# PCB-OLEDROCKER.net
KiCad netlist of a schematic drawn in EAGLE
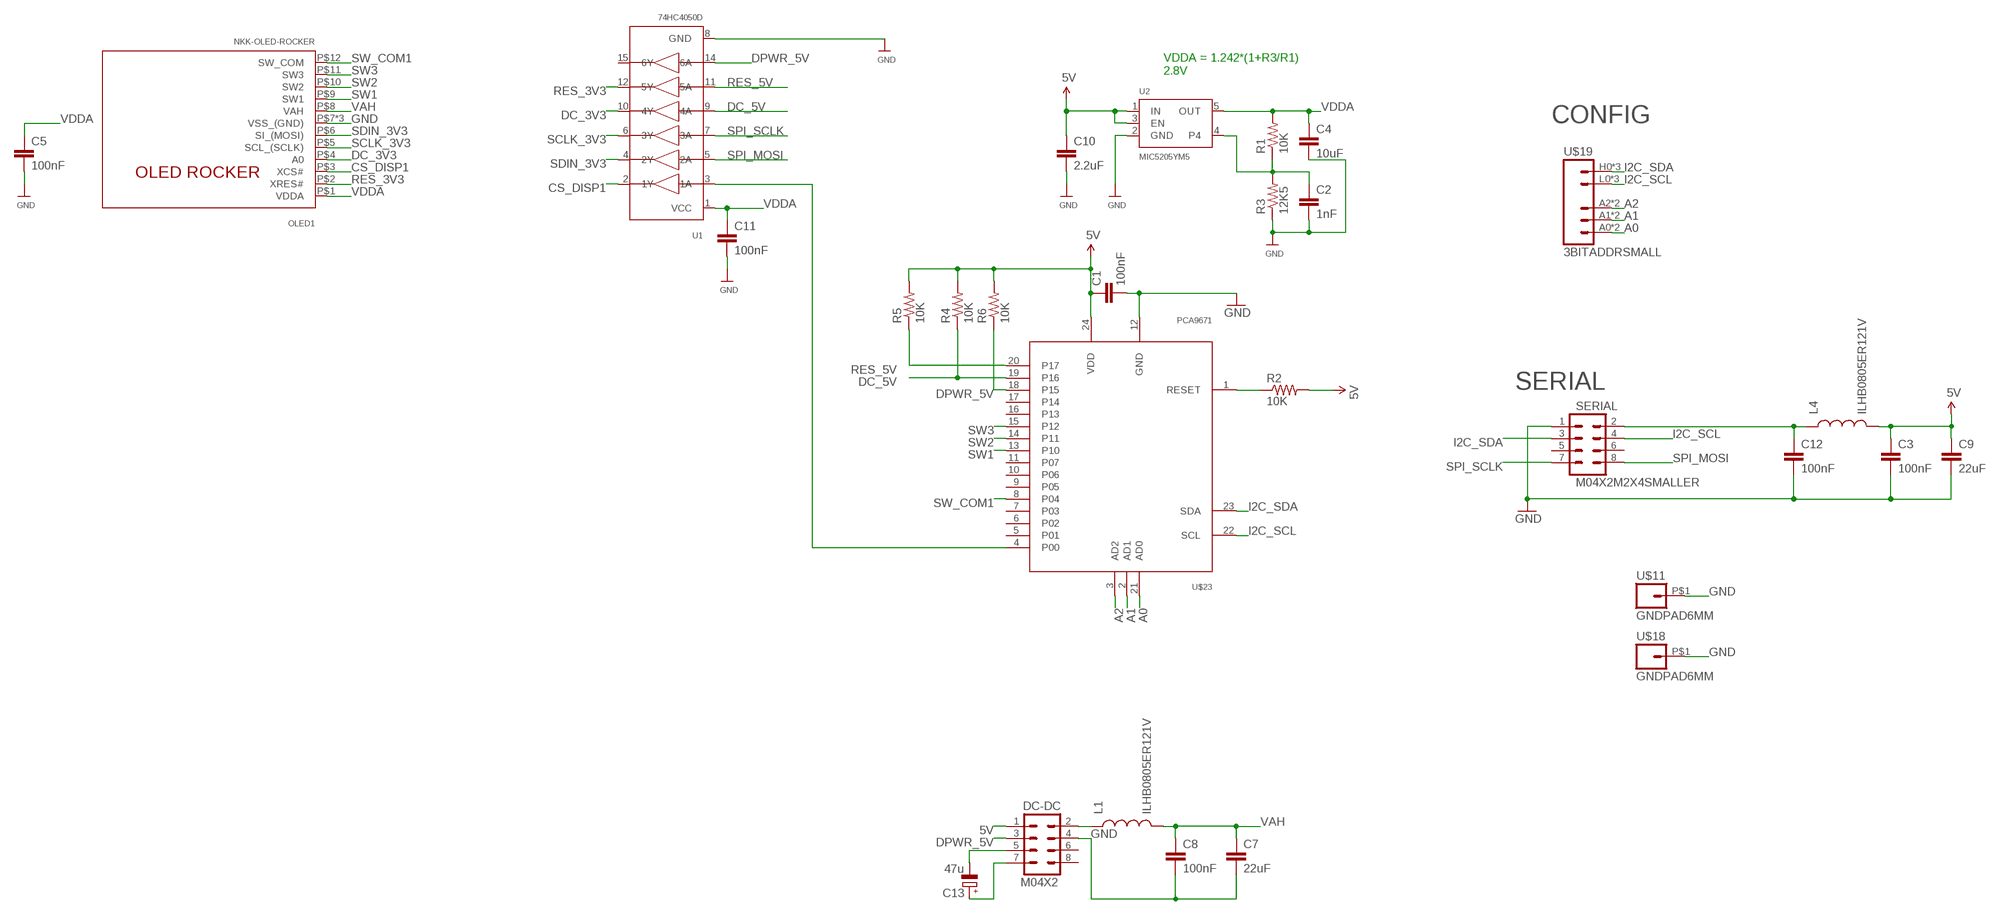
[diagram p0: schematic, sheet 1]

(export (version "E")
  (design (tool "Eeschema 10.0.6"))
  (components
    (comp (ref "C1")
      (value "100nF")
      (footprint "eagle-import:0603-CAP")
      (libsource (lib "eagle-import") (part "CAP0603-CAP"))
    )
    (comp (ref "C2")
      (value "1nF")
      (footprint "eagle-import:0603-CAP")
      (libsource (lib "eagle-import") (part "CAP0603-CAP"))
    )
    (comp (ref "C3")
      (value "100nF")
      (footprint "eagle-import:0603-CAP")
      (libsource (lib "eagle-import") (part "CAP0603-CAP"))
    )
    (comp (ref "C4")
      (value "10uF")
      (footprint "eagle-import:0805")
      (libsource (lib "eagle-import") (part "CAP0805"))
    )
    (comp (ref "C5")
      (value "100nF")
      (footprint "eagle-import:0603-CAP")
      (libsource (lib "eagle-import") (part "CAP0603-CAP"))
    )
    (comp (ref "C7")
      (value "22uF")
      (footprint "eagle-import:0805")
      (libsource (lib "eagle-import") (part "CAP0805"))
    )
    (comp (ref "C8")
      (value "100nF")
      (footprint "eagle-import:0603-CAP")
      (libsource (lib "eagle-import") (part "CAP0603-CAP"))
    )
    (comp (ref "C9")
      (value "22uF")
      (footprint "eagle-import:0805")
      (libsource (lib "eagle-import") (part "CAP0805"))
    )
    (comp (ref "C10")
      (value "2.2uF")
      (footprint "eagle-import:0603-CAP")
      (libsource (lib "eagle-import") (part "CAP0603-CAP"))
    )
    (comp (ref "C11")
      (value "100nF")
      (footprint "eagle-import:0603-CAP")
      (libsource (lib "eagle-import") (part "CAP0603-CAP"))
    )
    (comp (ref "C12")
      (value "100nF")
      (footprint "eagle-import:0603-CAP")
      (libsource (lib "eagle-import") (part "CAP0603-CAP"))
    )
    (comp (ref "C13")
      (value "47u")
      (footprint "eagle-import:PANASONIC_D")
      (libsource (lib "eagle-import") (part "CPOL-EUD"))
    )
    (comp (ref "DC-DC")
      (value "M04X2")
      (footprint "eagle-import:2X4")
      (libsource (lib "eagle-import") (part "SparkFun_M04X2"))
    )
    (comp (ref "L1")
      (value "ILHB0805ER121V")
      (footprint "eagle-import:0805")
      (libsource (lib "eagle-import") (part "INDUCTOR0805"))
    )
    (comp (ref "L4")
      (value "ILHB0805ER121V")
      (footprint "eagle-import:0805")
      (libsource (lib "eagle-import") (part "INDUCTOR0805"))
    )
    (comp (ref "OLED1")
      (value "NKK-OLED-ROCKER")
      (footprint "eagle-import:JST_BM12B-SURS")
      (libsource (lib "eagle-import") (part "NKK-OLED-ROCKER"))
    )
    (comp (ref "R1")
      (value "10K")
      (footprint "eagle-import:0603-RES")
      (libsource (lib "eagle-import") (part "RESISTOR0603-RES"))
    )
    (comp (ref "R2")
      (value "10K")
      (footprint "eagle-import:0603-RES")
      (libsource (lib "eagle-import") (part "RESISTOR0603-RES"))
    )
    (comp (ref "R3")
      (value "12K5")
      (footprint "eagle-import:0603-RES")
      (libsource (lib "eagle-import") (part "RESISTOR0603-RES"))
    )
    (comp (ref "R4")
      (value "10K")
      (footprint "eagle-import:0603-RES")
      (libsource (lib "eagle-import") (part "RESISTOR0603-RES"))
    )
    (comp (ref "R5")
      (value "10K")
      (footprint "eagle-import:0603-RES")
      (libsource (lib "eagle-import") (part "RESISTOR0603-RES"))
    )
    (comp (ref "R6")
      (value "10K")
      (footprint "eagle-import:0603-RES")
      (libsource (lib "eagle-import") (part "RESISTOR0603-RES"))
    )
    (comp (ref "SERIAL")
      (value "M04X2M2X4SMALLER")
      (footprint "eagle-import:M2X4SMALLER")
      (libsource (lib "eagle-import") (part "M04X2M2X4SMALLER"))
    )
    (comp (ref "U$11")
      (value "GNDPAD6MM")
      (footprint "eagle-import:3.2MMPAD6MM")
      (libsource (lib "eagle-import") (part "GNDPAD6MM"))
    )
    (comp (ref "U$18")
      (value "GNDPAD6MM")
      (footprint "eagle-import:3.2MMPAD6MM")
      (libsource (lib "eagle-import") (part "GNDPAD6MM"))
    )
    (comp (ref "U$19")
      (value "3BITADDRSMALL")
      (footprint "eagle-import:3BITADDR_SMALL")
      (libsource (lib "eagle-import") (part "3BITADDRSMALL"))
    )
    (comp (ref "U$23")
      (value "PCA9671")
      (footprint "eagle-import:TSSOP24")
      (libsource (lib "eagle-import") (part "PCA9671"))
    )
    (comp (ref "U1")
      (value "74HC4050D")
      (footprint "eagle-import:TSSOP16")
      (libsource (lib "eagle-import") (part "74HC4050DTSSOP16"))
    )
    (comp (ref "U2")
      (value "MIC5205YM5")
      (footprint "eagle-import:SOT23-5")
      (libsource (lib "eagle-import") (part "VREG_SOT23-5"))
    )
  )
  (nets
    (net (code "1") (name "5V") (class "Default")
      (node (ref "C1") (pin "1") (pinfunction "1_1") (pintype "passive"))
      (node (ref "C10") (pin "1") (pinfunction "1_1") (pintype "passive"))
      (node (ref "C3") (pin "1") (pinfunction "1_1") (pintype "passive"))
      (node (ref "C9") (pin "1") (pinfunction "1_1") (pintype "passive"))
      (node (ref "DC-DC") (pin "1") (pinfunction "1_1") (pintype "passive"))
      (node (ref "L4") (pin "2") (pinfunction "2_2") (pintype "passive"))
      (node (ref "R2") (pin "2") (pinfunction "2_2") (pintype "passive"))
      (node (ref "R4") (pin "2") (pinfunction "2_2") (pintype "passive"))
      (node (ref "R5") (pin "2") (pinfunction "2_2") (pintype "passive"))
      (node (ref "R6") (pin "2") (pinfunction "2_2") (pintype "passive"))
      (node (ref "U$23") (pin "24") (pinfunction "VDD_24") (pintype "power_in"))
      (node (ref "U2") (pin "1") (pinfunction "IN_1") (pintype "bidirectional"))
      (node (ref "U2") (pin "3") (pinfunction "EN_3") (pintype "bidirectional"))
    )
    (net (code "2") (name "A0") (class "Default")
      (node (ref "U$19") (pin "A0") (pinfunction "A0_A0") (pintype "passive"))
      (node (ref "U$19") (pin "AS0") (pinfunction "A0_AS0") (pintype "passive"))
      (node (ref "U$23") (pin "21") (pinfunction "AD0_21") (pintype "input"))
    )
    (net (code "3") (name "A1") (class "Default")
      (node (ref "U$19") (pin "A1") (pinfunction "A1_A1") (pintype "passive"))
      (node (ref "U$19") (pin "AS1") (pinfunction "A1_AS1") (pintype "passive"))
      (node (ref "U$23") (pin "2") (pinfunction "AD1_2") (pintype "input"))
    )
    (net (code "4") (name "A2") (class "Default")
      (node (ref "U$19") (pin "A2") (pinfunction "A2_A2") (pintype "passive"))
      (node (ref "U$19") (pin "AS2") (pinfunction "A2_AS2") (pintype "passive"))
      (node (ref "U$23") (pin "3") (pinfunction "AD2_3") (pintype "input"))
    )
    (net (code "5") (name "CS_DISP1") (class "Default")
      (node (ref "OLED1") (pin "P$3") (pinfunction "XCS#_P$3") (pintype "input"))
      (node (ref "U1") (pin "2") (pinfunction "1Y_2") (pintype "bidirectional"))
    )
    (net (code "6") (name "DC_3V3") (class "Default")
      (node (ref "OLED1") (pin "P$4") (pinfunction "A0_P$4") (pintype "input"))
      (node (ref "U1") (pin "10") (pinfunction "4Y_10") (pintype "bidirectional"))
    )
    (net (code "7") (name "DC_5V") (class "Default")
      (node (ref "R4") (pin "1") (pinfunction "1_1") (pintype "passive"))
      (node (ref "U$23") (pin "19") (pinfunction "P16_19") (pintype "output"))
      (node (ref "U1") (pin "9") (pinfunction "4A_9") (pintype "bidirectional"))
    )
    (net (code "8") (name "DPWR_5V") (class "Default")
      (node (ref "DC-DC") (pin "3") (pinfunction "3_3") (pintype "passive"))
      (node (ref "R6") (pin "1") (pinfunction "1_1") (pintype "passive"))
      (node (ref "U$23") (pin "18") (pinfunction "P15_18") (pintype "output"))
      (node (ref "U1") (pin "14") (pinfunction "6A_14") (pintype "bidirectional"))
    )
    (net (code "9") (name "GND") (class "Default")
      (node (ref "C1") (pin "2") (pinfunction "2_2") (pintype "passive"))
      (node (ref "C10") (pin "2") (pinfunction "2_2") (pintype "passive"))
      (node (ref "C11") (pin "2") (pinfunction "2_2") (pintype "passive"))
      (node (ref "C12") (pin "2") (pinfunction "2_2") (pintype "passive"))
      (node (ref "C2") (pin "2") (pinfunction "2_2") (pintype "passive"))
      (node (ref "C3") (pin "2") (pinfunction "2_2") (pintype "passive"))
      (node (ref "C4") (pin "2") (pinfunction "2_2") (pintype "passive"))
      (node (ref "C5") (pin "2") (pinfunction "2_2") (pintype "passive"))
      (node (ref "C7") (pin "2") (pinfunction "2_2") (pintype "passive"))
      (node (ref "C8") (pin "2") (pinfunction "2_2") (pintype "passive"))
      (node (ref "C9") (pin "2") (pinfunction "2_2") (pintype "passive"))
      (node (ref "DC-DC") (pin "4") (pinfunction "4_4") (pintype "passive"))
      (node (ref "OLED1") (pin "P$7") (pinfunction "VSS_(GND)_P$7") (pintype "power_in"))
      (node (ref "OLED1") (pin "SUPPORT1") (pinfunction "VSS_(GND)_SUPPORT1") (pintype "power_in"))
      (node (ref "OLED1") (pin "SUPPORT2") (pinfunction "VSS_(GND)_SUPPORT2") (pintype "power_in"))
      (node (ref "R3") (pin "1") (pinfunction "1_1") (pintype "passive"))
      (node (ref "SERIAL") (pin "1") (pinfunction "1_1") (pintype "passive"))
      (node (ref "U$11") (pin "P$1") (pinfunction "1_P$1") (pintype "passive"))
      (node (ref "U$18") (pin "P$1") (pinfunction "1_P$1") (pintype "passive"))
      (node (ref "U$23") (pin "12") (pinfunction "GND_12") (pintype "power_in"))
      (node (ref "U1") (pin "8") (pinfunction "GND_8") (pintype "bidirectional"))
      (node (ref "U2") (pin "2") (pinfunction "GND_2") (pintype "bidirectional"))
    )
    (net (code "10") (name "I2C_SCL") (class "Default")
      (node (ref "SERIAL") (pin "4") (pinfunction "4_4") (pintype "passive"))
      (node (ref "U$19") (pin "L0") (pinfunction "GND_L0") (pintype "passive"))
      (node (ref "U$19") (pin "L1") (pinfunction "GND_L1") (pintype "passive"))
      (node (ref "U$19") (pin "L2") (pinfunction "GND_L2") (pintype "passive"))
      (node (ref "U$23") (pin "22") (pinfunction "SCL_22") (pintype "input"))
    )
    (net (code "11") (name "I2C_SDA") (class "Default")
      (node (ref "SERIAL") (pin "3") (pinfunction "3_3") (pintype "passive"))
      (node (ref "U$19") (pin "H0") (pinfunction "VCC_H0") (pintype "passive"))
      (node (ref "U$19") (pin "H1") (pinfunction "VCC_H1") (pintype "passive"))
      (node (ref "U$19") (pin "H2") (pinfunction "VCC_H2") (pintype "passive"))
      (node (ref "U$23") (pin "23") (pinfunction "SDA_23") (pintype "input"))
    )
    (net (code "12") (name "Net-(C12-Pad1)") (class "Default")
      (node (ref "C12") (pin "1") (pinfunction "1_1") (pintype "passive"))
      (node (ref "L4") (pin "1") (pinfunction "1_1") (pintype "passive"))
      (node (ref "SERIAL") (pin "2") (pinfunction "2_2") (pintype "passive"))
    )
    (net (code "13") (name "Net-(C13-Pad+)") (class "Default")
      (node (ref "C13") (pin "+") (pinfunction "+_+") (pintype "passive"))
      (node (ref "DC-DC") (pin "7") (pinfunction "7_7") (pintype "passive"))
    )
    (net (code "14") (name "Net-(C13-Pad-)") (class "Default")
      (node (ref "C13") (pin "-") (pinfunction "-_-") (pintype "passive"))
      (node (ref "DC-DC") (pin "5") (pinfunction "5_5") (pintype "passive"))
    )
    (net (code "15") (name "Net-(DC-DC-Pad2)") (class "Default")
      (node (ref "DC-DC") (pin "2") (pinfunction "2_2") (pintype "passive"))
      (node (ref "L1") (pin "1") (pinfunction "1_1") (pintype "passive"))
    )
    (net (code "16") (name "Net-(U$23-P00)") (class "Default")
      (node (ref "U$23") (pin "4") (pinfunction "P00_4") (pintype "output"))
      (node (ref "U1") (pin "3") (pinfunction "1A_3") (pintype "bidirectional"))
    )
    (net (code "17") (name "Net-(U$23-RESET)") (class "Default")
      (node (ref "R2") (pin "1") (pinfunction "1_1") (pintype "passive"))
      (node (ref "U$23") (pin "1") (pinfunction "RESET_1") (pintype "input"))
    )
    (net (code "18") (name "Net-(U2-P4)") (class "Default")
      (node (ref "C2") (pin "1") (pinfunction "1_1") (pintype "passive"))
      (node (ref "R1") (pin "1") (pinfunction "1_1") (pintype "passive"))
      (node (ref "R3") (pin "2") (pinfunction "2_2") (pintype "passive"))
      (node (ref "U2") (pin "4") (pinfunction "P4_4") (pintype "bidirectional"))
    )
    (net (code "19") (name "RES_3V3") (class "Default")
      (node (ref "OLED1") (pin "P$2") (pinfunction "XRES#_P$2") (pintype "input"))
      (node (ref "U1") (pin "12") (pinfunction "5Y_12") (pintype "bidirectional"))
    )
    (net (code "20") (name "RES_5V") (class "Default")
      (node (ref "R5") (pin "1") (pinfunction "1_1") (pintype "passive"))
      (node (ref "U$23") (pin "20") (pinfunction "P17_20") (pintype "output"))
      (node (ref "U1") (pin "11") (pinfunction "5A_11") (pintype "bidirectional"))
    )
    (net (code "21") (name "SCLK_3V3") (class "Default")
      (node (ref "OLED1") (pin "P$5") (pinfunction "SCL_(SCLK)_P$5") (pintype "input"))
      (node (ref "U1") (pin "6") (pinfunction "3Y_6") (pintype "bidirectional"))
    )
    (net (code "22") (name "SDIN_3V3") (class "Default")
      (node (ref "OLED1") (pin "P$6") (pinfunction "SI_(MOSI)_P$6") (pintype "input"))
      (node (ref "U1") (pin "4") (pinfunction "2Y_4") (pintype "bidirectional"))
    )
    (net (code "23") (name "SPI_MOSI") (class "Default")
      (node (ref "SERIAL") (pin "8") (pinfunction "8_8") (pintype "passive"))
      (node (ref "U1") (pin "5") (pinfunction "2A_5") (pintype "bidirectional"))
    )
    (net (code "24") (name "SPI_SCLK") (class "Default")
      (node (ref "SERIAL") (pin "7") (pinfunction "7_7") (pintype "passive"))
      (node (ref "U1") (pin "7") (pinfunction "3A_7") (pintype "bidirectional"))
    )
    (net (code "25") (name "SW1") (class "Default")
      (node (ref "OLED1") (pin "P$9") (pinfunction "SW1_P$9") (pintype "bidirectional"))
      (node (ref "U$23") (pin "13") (pinfunction "P10_13") (pintype "output"))
    )
    (net (code "26") (name "SW2") (class "Default")
      (node (ref "OLED1") (pin "P$10") (pinfunction "SW2_P$10") (pintype "bidirectional"))
      (node (ref "U$23") (pin "14") (pinfunction "P11_14") (pintype "output"))
    )
    (net (code "27") (name "SW3") (class "Default")
      (node (ref "OLED1") (pin "P$11") (pinfunction "SW3_P$11") (pintype "bidirectional"))
      (node (ref "U$23") (pin "15") (pinfunction "P12_15") (pintype "output"))
    )
    (net (code "28") (name "SW_COM1") (class "Default")
      (node (ref "OLED1") (pin "P$12") (pinfunction "SW_COM_P$12") (pintype "bidirectional"))
      (node (ref "U$23") (pin "8") (pinfunction "P04_8") (pintype "output"))
    )
    (net (code "29") (name "VAH") (class "Default")
      (node (ref "C7") (pin "1") (pinfunction "1_1") (pintype "passive"))
      (node (ref "C8") (pin "1") (pinfunction "1_1") (pintype "passive"))
      (node (ref "L1") (pin "2") (pinfunction "2_2") (pintype "passive"))
      (node (ref "OLED1") (pin "P$8") (pinfunction "VAH_P$8") (pintype "power_in"))
    )
    (net (code "30") (name "VDDA") (class "Default")
      (node (ref "C11") (pin "1") (pinfunction "1_1") (pintype "passive"))
      (node (ref "C4") (pin "1") (pinfunction "1_1") (pintype "passive"))
      (node (ref "C5") (pin "1") (pinfunction "1_1") (pintype "passive"))
      (node (ref "OLED1") (pin "P$1") (pinfunction "VDDA_P$1") (pintype "power_in"))
      (node (ref "R1") (pin "2") (pinfunction "2_2") (pintype "passive"))
      (node (ref "U1") (pin "1") (pinfunction "VCC_1") (pintype "bidirectional"))
      (node (ref "U2") (pin "5") (pinfunction "OUT_5") (pintype "bidirectional"))
    )
    (net (code "31") (name "unconnected-(DC-DC-Pad6)") (class "Default")
      (node (ref "DC-DC") (pin "6") (pinfunction "6_6") (pintype "passive"))
    )
    (net (code "32") (name "unconnected-(DC-DC-Pad8)") (class "Default")
      (node (ref "DC-DC") (pin "8") (pinfunction "8_8") (pintype "passive"))
    )
    (net (code "33") (name "unconnected-(SERIAL-Pad5)") (class "Default")
      (node (ref "SERIAL") (pin "5") (pinfunction "5_5") (pintype "passive"))
    )
    (net (code "34") (name "unconnected-(SERIAL-Pad6)") (class "Default")
      (node (ref "SERIAL") (pin "6") (pinfunction "6_6") (pintype "passive"))
    )
    (net (code "35") (name "unconnected-(U$23-P01-Pad5)") (class "Default")
      (node (ref "U$23") (pin "5") (pinfunction "P01_5") (pintype "output"))
    )
    (net (code "36") (name "unconnected-(U$23-P02-Pad6)") (class "Default")
      (node (ref "U$23") (pin "6") (pinfunction "P02_6") (pintype "output"))
    )
    (net (code "37") (name "unconnected-(U$23-P03-Pad7)") (class "Default")
      (node (ref "U$23") (pin "7") (pinfunction "P03_7") (pintype "output"))
    )
    (net (code "38") (name "unconnected-(U$23-P05-Pad9)") (class "Default")
      (node (ref "U$23") (pin "9") (pinfunction "P05_9") (pintype "output"))
    )
    (net (code "39") (name "unconnected-(U$23-P06-Pad10)") (class "Default")
      (node (ref "U$23") (pin "10") (pinfunction "P06_10") (pintype "output"))
    )
    (net (code "40") (name "unconnected-(U$23-P07-Pad11)") (class "Default")
      (node (ref "U$23") (pin "11") (pinfunction "P07_11") (pintype "output"))
    )
    (net (code "41") (name "unconnected-(U$23-P13-Pad16)") (class "Default")
      (node (ref "U$23") (pin "16") (pinfunction "P13_16") (pintype "output"))
    )
    (net (code "42") (name "unconnected-(U$23-P14-Pad17)") (class "Default")
      (node (ref "U$23") (pin "17") (pinfunction "P14_17") (pintype "output"))
    )
    (net (code "43") (name "unconnected-(U1-6Y-Pad15)") (class "Default")
      (node (ref "U1") (pin "15") (pinfunction "6Y_15") (pintype "bidirectional"))
    )
  )
)
